# DDR3_16bits.net
KiCad netlist of a schematic drawn in Altium Designer
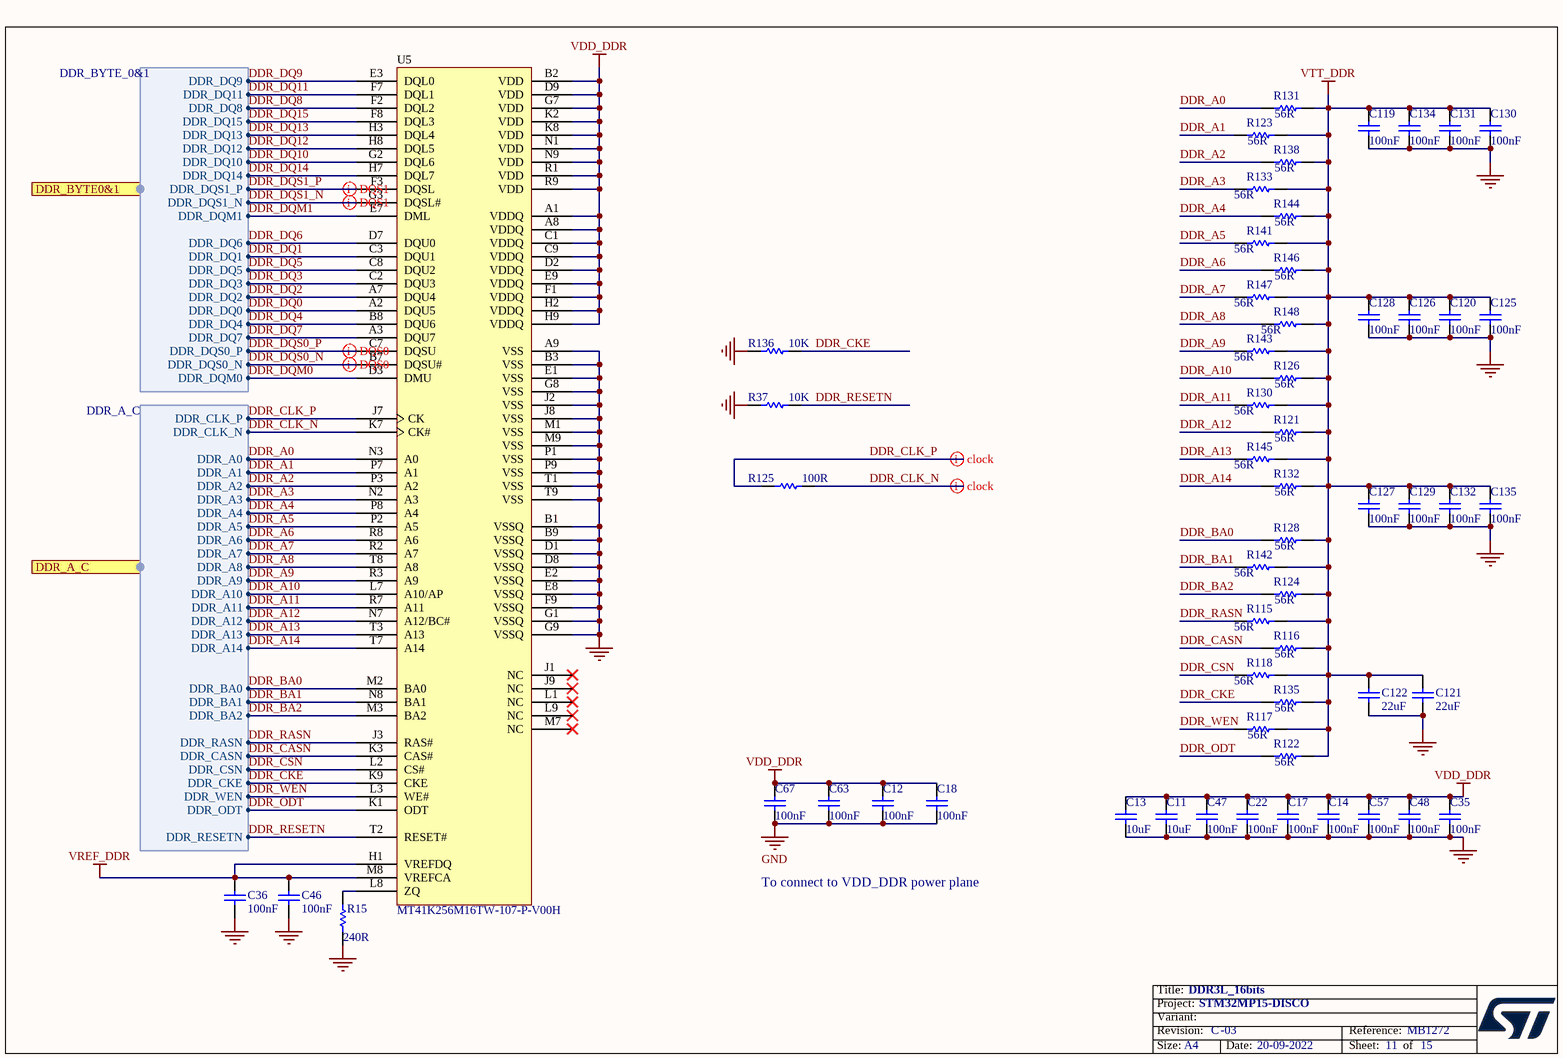
[diagram p0: DDR3_16bits.SchDoc]

(export (version "E")
  (design (tool "Eeschema 10.0.6"))
  (components
    (comp (ref "C11")
      (value "10uF")
      (footprint "C0603")
      (description "Capacitor, MLCC, 10uF, 10V, X5R, 10%, 0603, T=0,8mm")
      (fields
        (field (name "INTERNAL_PART_NUMBER") "MCD-00099")
        (field (name "MANUFACTURER_PART_NUMBER") "GRM188R61A106KE69D")
        (field (name "PROVIDED_BY") "SUBCO")
      )
      (libsource (lib "MCD_PARTS_database") (part "Capacitor"))
    )
    (comp (ref "C12")
      (value "100nF")
      (footprint "C0402")
      (description "Capacitor, MLCC, 100nF, 16V, X7R, 10%, 0402, T=0.5mm")
      (fields
        (field (name "INTERNAL_PART_NUMBER") "MCD-00006")
        (field (name "MANUFACTURER_PART_NUMBER") "CC0402KRX7R7BB104")
        (field (name "PROVIDED_BY") "SUBCO")
      )
      (libsource (lib "MCD_PARTS_database") (part "Capacitor"))
    )
    (comp (ref "C13")
      (value "10uF")
      (footprint "C0603")
      (description "Capacitor, MLCC, 10uF, 10V, X5R, 10%, 0603, T=0,8mm")
      (fields
        (field (name "INTERNAL_PART_NUMBER") "MCD-00099")
        (field (name "MANUFACTURER_PART_NUMBER") "GRM188R61A106KE69D")
        (field (name "PROVIDED_BY") "SUBCO")
      )
      (libsource (lib "MCD_PARTS_database") (part "Capacitor"))
    )
    (comp (ref "C14")
      (value "100nF")
      (footprint "C0402")
      (description "Capacitor,100nF,16V,X7R,10%,0402")
      (fields
        (field (name "INTERNAL_PART_NUMBER") "MCD-00006")
        (field (name "MANUFACTURER_PART_NUMBER") "CC0402KRX7R7BB104")
        (field (name "PROVIDED_BY") "SUBCO")
      )
      (libsource (lib "MCD_PARTS_database") (part "Capacitor"))
    )
    (comp (ref "C17")
      (value "100nF")
      (footprint "C0402")
      (description "Capacitor,100nF,16V,X7R,10%,0402")
      (fields
        (field (name "INTERNAL_PART_NUMBER") "MCD-00006")
        (field (name "MANUFACTURER_PART_NUMBER") "CC0402KRX7R7BB104")
        (field (name "PROVIDED_BY") "SUBCO")
      )
      (libsource (lib "MCD_PARTS_database") (part "Capacitor"))
    )
    (comp (ref "C18")
      (value "100nF")
      (footprint "C0402")
      (description "Capacitor, MLCC, 100nF, 16V, X7R, 10%, 0402, T=0.5mm")
      (fields
        (field (name "INTERNAL_PART_NUMBER") "MCD-00006")
        (field (name "MANUFACTURER_PART_NUMBER") "CC0402KRX7R7BB104")
        (field (name "PROVIDED_BY") "SUBCO")
      )
      (libsource (lib "MCD_PARTS_database") (part "Capacitor"))
    )
    (comp (ref "C22")
      (value "100nF")
      (footprint "C0402")
      (description "Capacitor,100nF,16V,X7R,10%,0402")
      (fields
        (field (name "INTERNAL_PART_NUMBER") "MCD-00006")
        (field (name "MANUFACTURER_PART_NUMBER") "CC0402KRX7R7BB104")
        (field (name "PROVIDED_BY") "SUBCO")
      )
      (libsource (lib "MCD_PARTS_database") (part "Capacitor"))
    )
    (comp (ref "C35")
      (value "100nF")
      (footprint "C0402")
      (description "Capacitor,100nF,16V,X7R,10%,0402")
      (fields
        (field (name "INTERNAL_PART_NUMBER") "MCD-00006")
        (field (name "MANUFACTURER_PART_NUMBER") "CC0402KRX7R7BB104")
        (field (name "PROVIDED_BY") "SUBCO")
      )
      (libsource (lib "MCD_PARTS_database") (part "Capacitor"))
    )
    (comp (ref "C36")
      (value "100nF")
      (footprint "C0402")
      (description "Capacitor,100nF,16V,X7R,10%,0402")
      (fields
        (field (name "INTERNAL_PART_NUMBER") "MCD-00006")
        (field (name "MANUFACTURER_PART_NUMBER") "CC0402KRX7R7BB104")
        (field (name "PROVIDED_BY") "SUBCO")
      )
      (libsource (lib "MCD_PARTS_database") (part "Capacitor"))
    )
    (comp (ref "C46")
      (value "100nF")
      (footprint "C0402")
      (description "Capacitor,100nF,16V,X7R,10%,0402")
      (fields
        (field (name "INTERNAL_PART_NUMBER") "MCD-00006")
        (field (name "MANUFACTURER_PART_NUMBER") "CC0402KRX7R7BB104")
        (field (name "PROVIDED_BY") "SUBCO")
      )
      (libsource (lib "MCD_PARTS_database") (part "Capacitor"))
    )
    (comp (ref "C47")
      (value "100nF")
      (footprint "C0402")
      (description "Capacitor,100nF,16V,X7R,10%,0402")
      (fields
        (field (name "INTERNAL_PART_NUMBER") "MCD-00006")
        (field (name "MANUFACTURER_PART_NUMBER") "CC0402KRX7R7BB104")
        (field (name "PROVIDED_BY") "SUBCO")
      )
      (libsource (lib "MCD_PARTS_database") (part "Capacitor"))
    )
    (comp (ref "C48")
      (value "100nF")
      (footprint "C0402")
      (description "Capacitor,100nF,16V,X7R,10%,0402")
      (fields
        (field (name "INTERNAL_PART_NUMBER") "MCD-00006")
        (field (name "MANUFACTURER_PART_NUMBER") "CC0402KRX7R7BB104")
        (field (name "PROVIDED_BY") "SUBCO")
      )
      (libsource (lib "MCD_PARTS_database") (part "Capacitor"))
    )
    (comp (ref "C57")
      (value "100nF")
      (footprint "C0402")
      (description "Capacitor,100nF,16V,X7R,10%,0402")
      (fields
        (field (name "INTERNAL_PART_NUMBER") "MCD-00006")
        (field (name "MANUFACTURER_PART_NUMBER") "CC0402KRX7R7BB104")
        (field (name "PROVIDED_BY") "SUBCO")
      )
      (libsource (lib "MCD_PARTS_database") (part "Capacitor"))
    )
    (comp (ref "C63")
      (value "100nF")
      (footprint "C0402")
      (description "Capacitor, MLCC, 100nF, 16V, X7R, 10%, 0402, T=0.5mm")
      (fields
        (field (name "INTERNAL_PART_NUMBER") "MCD-00006")
        (field (name "MANUFACTURER_PART_NUMBER") "CC0402KRX7R7BB104")
        (field (name "PROVIDED_BY") "SUBCO")
      )
      (libsource (lib "MCD_PARTS_database") (part "Capacitor"))
    )
    (comp (ref "C67")
      (value "100nF")
      (footprint "C0402")
      (description "Capacitor, MLCC, 100nF, 16V, X7R, 10%, 0402, T=0.5mm")
      (fields
        (field (name "INTERNAL_PART_NUMBER") "MCD-00006")
        (field (name "MANUFACTURER_PART_NUMBER") "CC0402KRX7R7BB104")
        (field (name "PROVIDED_BY") "SUBCO")
      )
      (libsource (lib "MCD_PARTS_database") (part "Capacitor"))
    )
    (comp (ref "C119")
      (value "100nF")
      (footprint "C0402")
      (description "Capacitor,100nF,16V,X7R,10%,0402")
      (fields
        (field (name "INTERNAL_PART_NUMBER") "MCD-00006")
        (field (name "MANUFACTURER_PART_NUMBER") "CC0402KRX7R7BB104")
        (field (name "PROVIDED_BY") "SUBCO")
      )
      (libsource (lib "MCD_PARTS_database") (part "Capacitor"))
    )
    (comp (ref "C120")
      (value "100nF")
      (footprint "C0402")
      (description "Capacitor,100nF,16V,X7R,10%,0402")
      (fields
        (field (name "INTERNAL_PART_NUMBER") "MCD-00006")
        (field (name "MANUFACTURER_PART_NUMBER") "CC0402KRX7R7BB104")
        (field (name "PROVIDED_BY") "SUBCO")
      )
      (libsource (lib "MCD_PARTS_database") (part "Capacitor"))
    )
    (comp (ref "C121")
      (value "22uF")
      (footprint "C0603")
      (description "Capacitor, MLCC, 22uF, 6V3, X5R, 20%, 0603, T=0,8mm")
      (fields
        (field (name "INTERNAL_PART_NUMBER") "MCD-00100")
        (field (name "MANUFACTURER_PART_NUMBER") "GRM188R60J226MEA0J")
        (field (name "PROVIDED_BY") "SUBCO")
      )
      (libsource (lib "MCD_PARTS_database") (part "Capacitor"))
    )
    (comp (ref "C122")
      (value "22uF")
      (footprint "C0603")
      (description "Capacitor, MLCC, 22uF, 6V3, X5R, 20%, 0603, T=0,8mm")
      (fields
        (field (name "INTERNAL_PART_NUMBER") "MCD-00100")
        (field (name "MANUFACTURER_PART_NUMBER") "GRM188R60J226MEA0J")
        (field (name "PROVIDED_BY") "SUBCO")
      )
      (libsource (lib "MCD_PARTS_database") (part "Capacitor"))
    )
    (comp (ref "C125")
      (value "100nF")
      (footprint "C0402")
      (description "Capacitor,100nF,16V,X7R,10%,0402")
      (fields
        (field (name "INTERNAL_PART_NUMBER") "MCD-00006")
        (field (name "MANUFACTURER_PART_NUMBER") "CC0402KRX7R7BB104")
        (field (name "PROVIDED_BY") "SUBCO")
      )
      (libsource (lib "MCD_PARTS_database") (part "Capacitor"))
    )
    (comp (ref "C126")
      (value "100nF")
      (footprint "C0402")
      (description "Capacitor,100nF,16V,X7R,10%,0402")
      (fields
        (field (name "INTERNAL_PART_NUMBER") "MCD-00006")
        (field (name "MANUFACTURER_PART_NUMBER") "CC0402KRX7R7BB104")
        (field (name "PROVIDED_BY") "SUBCO")
      )
      (libsource (lib "MCD_PARTS_database") (part "Capacitor"))
    )
    (comp (ref "C127")
      (value "100nF")
      (footprint "C0402")
      (description "Capacitor,100nF,16V,X7R,10%,0402")
      (fields
        (field (name "INTERNAL_PART_NUMBER") "MCD-00006")
        (field (name "MANUFACTURER_PART_NUMBER") "CC0402KRX7R7BB104")
        (field (name "PROVIDED_BY") "SUBCO")
      )
      (libsource (lib "MCD_PARTS_database") (part "Capacitor"))
    )
    (comp (ref "C128")
      (value "100nF")
      (footprint "C0402")
      (description "Capacitor,100nF,16V,X7R,10%,0402")
      (fields
        (field (name "INTERNAL_PART_NUMBER") "MCD-00006")
        (field (name "MANUFACTURER_PART_NUMBER") "CC0402KRX7R7BB104")
        (field (name "PROVIDED_BY") "SUBCO")
      )
      (libsource (lib "MCD_PARTS_database") (part "Capacitor"))
    )
    (comp (ref "C129")
      (value "100nF")
      (footprint "C0402")
      (description "Capacitor,100nF,16V,X7R,10%,0402")
      (fields
        (field (name "INTERNAL_PART_NUMBER") "MCD-00006")
        (field (name "MANUFACTURER_PART_NUMBER") "CC0402KRX7R7BB104")
        (field (name "PROVIDED_BY") "SUBCO")
      )
      (libsource (lib "MCD_PARTS_database") (part "Capacitor"))
    )
    (comp (ref "C130")
      (value "100nF")
      (footprint "C0402")
      (description "Capacitor,100nF,16V,X7R,10%,0402")
      (fields
        (field (name "INTERNAL_PART_NUMBER") "MCD-00006")
        (field (name "MANUFACTURER_PART_NUMBER") "CC0402KRX7R7BB104")
        (field (name "PROVIDED_BY") "SUBCO")
      )
      (libsource (lib "MCD_PARTS_database") (part "Capacitor"))
    )
    (comp (ref "C131")
      (value "100nF")
      (footprint "C0402")
      (description "Capacitor,100nF,16V,X7R,10%,0402")
      (fields
        (field (name "INTERNAL_PART_NUMBER") "MCD-00006")
        (field (name "MANUFACTURER_PART_NUMBER") "CC0402KRX7R7BB104")
        (field (name "PROVIDED_BY") "SUBCO")
      )
      (libsource (lib "MCD_PARTS_database") (part "Capacitor"))
    )
    (comp (ref "C132")
      (value "100nF")
      (footprint "C0402")
      (description "Capacitor,100nF,16V,X7R,10%,0402")
      (fields
        (field (name "INTERNAL_PART_NUMBER") "MCD-00006")
        (field (name "MANUFACTURER_PART_NUMBER") "CC0402KRX7R7BB104")
        (field (name "PROVIDED_BY") "SUBCO")
      )
      (libsource (lib "MCD_PARTS_database") (part "Capacitor"))
    )
    (comp (ref "C134")
      (value "100nF")
      (footprint "C0402")
      (description "Capacitor,100nF,16V,X7R,10%,0402")
      (fields
        (field (name "INTERNAL_PART_NUMBER") "MCD-00006")
        (field (name "MANUFACTURER_PART_NUMBER") "CC0402KRX7R7BB104")
        (field (name "PROVIDED_BY") "SUBCO")
      )
      (libsource (lib "MCD_PARTS_database") (part "Capacitor"))
    )
    (comp (ref "C135")
      (value "100nF")
      (footprint "C0402")
      (description "Capacitor,100nF,16V,X7R,10%,0402")
      (fields
        (field (name "INTERNAL_PART_NUMBER") "MCD-00006")
        (field (name "MANUFACTURER_PART_NUMBER") "CC0402KRX7R7BB104")
        (field (name "PROVIDED_BY") "SUBCO")
      )
      (libsource (lib "MCD_PARTS_database") (part "Capacitor"))
    )
    (comp (ref "R15")
      (value "240R")
      (footprint "R0402")
      (description "Resistor,240R,0402,1%,1/16W")
      (fields
        (field (name "INTERNAL_PART_NUMBER") "MCD-00120")
        (field (name "MANUFACTURER_PART_NUMBER") "RC0402FR-07240RL")
        (field (name "PROVIDED_BY") "SUBCO")
      )
      (libsource (lib "MCD_PARTS_database") (part "Resistor"))
    )
    (comp (ref "R37")
      (value "10K")
      (footprint "R0402")
      (description "Resistor,10K,0402,1%,1/16W")
      (fields
        (field (name "INTERNAL_PART_NUMBER") "MCD-00053")
        (field (name "MANUFACTURER_PART_NUMBER") "RC0402FR-0710KL")
        (field (name "PROVIDED_BY") "SUBCO")
      )
      (libsource (lib "MCD_PARTS_database") (part "Resistor"))
    )
    (comp (ref "R115")
      (value "56R")
      (footprint "R0402")
      (description "Resistor, 56R, 0402, +/-1%, 1/16W")
      (fields
        (field (name "INTERNAL_PART_NUMBER") "MCD-00054")
        (field (name "MANUFACTURER_PART_NUMBER") "RC0402FR-0756RL")
      )
      (libsource (lib "MCD_PARTS_database") (part "Resistor"))
    )
    (comp (ref "R116")
      (value "56R")
      (footprint "R0402")
      (description "Resistor, 56R, 0402, +/-1%, 1/16W")
      (fields
        (field (name "INTERNAL_PART_NUMBER") "MCD-00054")
        (field (name "MANUFACTURER_PART_NUMBER") "RC0402FR-0756RL")
      )
      (libsource (lib "MCD_PARTS_database") (part "Resistor"))
    )
    (comp (ref "R117")
      (value "56R")
      (footprint "R0402")
      (description "Resistor, 56R, 0402, +/-1%, 1/16W")
      (fields
        (field (name "INTERNAL_PART_NUMBER") "MCD-00054")
        (field (name "MANUFACTURER_PART_NUMBER") "RC0402FR-0756RL")
      )
      (libsource (lib "MCD_PARTS_database") (part "Resistor"))
    )
    (comp (ref "R118")
      (value "56R")
      (footprint "R0402")
      (description "Resistor, 56R, 0402, +/-1%, 1/16W")
      (fields
        (field (name "INTERNAL_PART_NUMBER") "MCD-00054")
        (field (name "MANUFACTURER_PART_NUMBER") "RC0402FR-0756RL")
      )
      (libsource (lib "MCD_PARTS_database") (part "Resistor"))
    )
    (comp (ref "R121")
      (value "56R")
      (footprint "R0402")
      (description "Resistor, 56R, 0402, +/-1%, 1/16W")
      (fields
        (field (name "INTERNAL_PART_NUMBER") "MCD-00054")
        (field (name "MANUFACTURER_PART_NUMBER") "RC0402FR-0756RL")
      )
      (libsource (lib "MCD_PARTS_database") (part "Resistor"))
    )
    (comp (ref "R122")
      (value "56R")
      (footprint "R0402")
      (description "Resistor, 56R, 0402, +/-1%, 1/16W")
      (fields
        (field (name "INTERNAL_PART_NUMBER") "MCD-00054")
        (field (name "MANUFACTURER_PART_NUMBER") "RC0402FR-0756RL")
      )
      (libsource (lib "MCD_PARTS_database") (part "Resistor"))
    )
    (comp (ref "R123")
      (value "56R")
      (footprint "R0402")
      (description "Resistor, 56R, 0402, +/-1%, 1/16W")
      (fields
        (field (name "INTERNAL_PART_NUMBER") "MCD-00054")
        (field (name "MANUFACTURER_PART_NUMBER") "RC0402FR-0756RL")
      )
      (libsource (lib "MCD_PARTS_database") (part "Resistor"))
    )
    (comp (ref "R124")
      (value "56R")
      (footprint "R0402")
      (description "Resistor, 56R, 0402, +/-1%, 1/16W")
      (fields
        (field (name "INTERNAL_PART_NUMBER") "MCD-00054")
        (field (name "MANUFACTURER_PART_NUMBER") "RC0402FR-0756RL")
      )
      (libsource (lib "MCD_PARTS_database") (part "Resistor"))
    )
    (comp (ref "R125")
      (value "100R")
      (footprint "R0402")
      (description "Resistor,100R,0402,1%,1/16W")
      (fields
        (field (name "INTERNAL_PART_NUMBER") "MCD-00067")
        (field (name "MANUFACTURER_PART_NUMBER") "RC0402FR-07100RL")
        (field (name "PROVIDED_BY") "SUBCO")
      )
      (libsource (lib "MCD_PARTS_database") (part "Resistor"))
    )
    (comp (ref "R126")
      (value "56R")
      (footprint "R0402")
      (description "Resistor, 56R, 0402, +/-1%, 1/16W")
      (fields
        (field (name "INTERNAL_PART_NUMBER") "MCD-00054")
        (field (name "MANUFACTURER_PART_NUMBER") "RC0402FR-0756RL")
      )
      (libsource (lib "MCD_PARTS_database") (part "Resistor"))
    )
    (comp (ref "R128")
      (value "56R")
      (footprint "R0402")
      (description "Resistor, 56R, 0402, +/-1%, 1/16W")
      (fields
        (field (name "INTERNAL_PART_NUMBER") "MCD-00054")
        (field (name "MANUFACTURER_PART_NUMBER") "RC0402FR-0756RL")
      )
      (libsource (lib "MCD_PARTS_database") (part "Resistor"))
    )
    (comp (ref "R130")
      (value "56R")
      (footprint "R0402")
      (description "Resistor, 56R, 0402, +/-1%, 1/16W")
      (fields
        (field (name "INTERNAL_PART_NUMBER") "MCD-00054")
        (field (name "MANUFACTURER_PART_NUMBER") "RC0402FR-0756RL")
      )
      (libsource (lib "MCD_PARTS_database") (part "Resistor"))
    )
    (comp (ref "R131")
      (value "56R")
      (footprint "R0402")
      (description "Resistor, 56R, 0402, +/-1%, 1/16W")
      (fields
        (field (name "INTERNAL_PART_NUMBER") "MCD-00054")
        (field (name "MANUFACTURER_PART_NUMBER") "RC0402FR-0756RL")
      )
      (libsource (lib "MCD_PARTS_database") (part "Resistor"))
    )
    (comp (ref "R132")
      (value "56R")
      (footprint "R0402")
      (description "Resistor, 56R, 0402, +/-1%, 1/16W")
      (fields
        (field (name "INTERNAL_PART_NUMBER") "MCD-00054")
        (field (name "MANUFACTURER_PART_NUMBER") "RC0402FR-0756RL")
      )
      (libsource (lib "MCD_PARTS_database") (part "Resistor"))
    )
    (comp (ref "R133")
      (value "56R")
      (footprint "R0402")
      (description "Resistor, 56R, 0402, +/-1%, 1/16W")
      (fields
        (field (name "INTERNAL_PART_NUMBER") "MCD-00054")
        (field (name "MANUFACTURER_PART_NUMBER") "RC0402FR-0756RL")
      )
      (libsource (lib "MCD_PARTS_database") (part "Resistor"))
    )
    (comp (ref "R135")
      (value "56R")
      (footprint "R0402")
      (description "Resistor, 56R, 0402, +/-1%, 1/16W")
      (fields
        (field (name "INTERNAL_PART_NUMBER") "MCD-00054")
        (field (name "MANUFACTURER_PART_NUMBER") "RC0402FR-0756RL")
      )
      (libsource (lib "MCD_PARTS_database") (part "Resistor"))
    )
    (comp (ref "R136")
      (value "10K")
      (footprint "R0402")
      (description "Resistor,10K,0402,1%,1/16W")
      (fields
        (field (name "INTERNAL_PART_NUMBER") "MCD-00053")
        (field (name "MANUFACTURER_PART_NUMBER") "RC0402FR-0710KL")
        (field (name "PROVIDED_BY") "SUBCO")
      )
      (libsource (lib "MCD_PARTS_database") (part "Resistor"))
    )
    (comp (ref "R138")
      (value "56R")
      (footprint "R0402")
      (description "Resistor, 56R, 0402, +/-1%, 1/16W")
      (fields
        (field (name "INTERNAL_PART_NUMBER") "MCD-00054")
        (field (name "MANUFACTURER_PART_NUMBER") "RC0402FR-0756RL")
      )
      (libsource (lib "MCD_PARTS_database") (part "Resistor"))
    )
    (comp (ref "R141")
      (value "56R")
      (footprint "R0402")
      (description "Resistor, 56R, 0402, +/-1%, 1/16W")
      (fields
        (field (name "INTERNAL_PART_NUMBER") "MCD-00054")
        (field (name "MANUFACTURER_PART_NUMBER") "RC0402FR-0756RL")
      )
      (libsource (lib "MCD_PARTS_database") (part "Resistor"))
    )
    (comp (ref "R142")
      (value "56R")
      (footprint "R0402")
      (description "Resistor, 56R, 0402, +/-1%, 1/16W")
      (fields
        (field (name "INTERNAL_PART_NUMBER") "MCD-00054")
        (field (name "MANUFACTURER_PART_NUMBER") "RC0402FR-0756RL")
      )
      (libsource (lib "MCD_PARTS_database") (part "Resistor"))
    )
    (comp (ref "R143")
      (value "56R")
      (footprint "R0402")
      (description "Resistor, 56R, 0402, +/-1%, 1/16W")
      (fields
        (field (name "INTERNAL_PART_NUMBER") "MCD-00054")
        (field (name "MANUFACTURER_PART_NUMBER") "RC0402FR-0756RL")
      )
      (libsource (lib "MCD_PARTS_database") (part "Resistor"))
    )
    (comp (ref "R144")
      (value "56R")
      (footprint "R0402")
      (description "Resistor, 56R, 0402, +/-1%, 1/16W")
      (fields
        (field (name "INTERNAL_PART_NUMBER") "MCD-00054")
        (field (name "MANUFACTURER_PART_NUMBER") "RC0402FR-0756RL")
      )
      (libsource (lib "MCD_PARTS_database") (part "Resistor"))
    )
    (comp (ref "R145")
      (value "56R")
      (footprint "R0402")
      (description "Resistor, 56R, 0402, +/-1%, 1/16W")
      (fields
        (field (name "INTERNAL_PART_NUMBER") "MCD-00054")
        (field (name "MANUFACTURER_PART_NUMBER") "RC0402FR-0756RL")
      )
      (libsource (lib "MCD_PARTS_database") (part "Resistor"))
    )
    (comp (ref "R146")
      (value "56R")
      (footprint "R0402")
      (description "Resistor, 56R, 0402, +/-1%, 1/16W")
      (fields
        (field (name "INTERNAL_PART_NUMBER") "MCD-00054")
        (field (name "MANUFACTURER_PART_NUMBER") "RC0402FR-0756RL")
      )
      (libsource (lib "MCD_PARTS_database") (part "Resistor"))
    )
    (comp (ref "R147")
      (value "56R")
      (footprint "R0402")
      (description "Resistor, 56R, 0402, +/-1%, 1/16W")
      (fields
        (field (name "INTERNAL_PART_NUMBER") "MCD-00054")
        (field (name "MANUFACTURER_PART_NUMBER") "RC0402FR-0756RL")
      )
      (libsource (lib "MCD_PARTS_database") (part "Resistor"))
    )
    (comp (ref "R148")
      (value "56R")
      (footprint "R0402")
      (description "Resistor, 56R, 0402, +/-1%, 1/16W")
      (fields
        (field (name "INTERNAL_PART_NUMBER") "MCD-00054")
        (field (name "MANUFACTURER_PART_NUMBER") "RC0402FR-0756RL")
      )
      (libsource (lib "MCD_PARTS_database") (part "Resistor"))
    )
    (comp (ref "U5")
      (value "MT41K256M16TW-107-P-V00H")
      (footprint "ICC_FBGA96_8X14_P080")
      (description "Memory,DDR3L,4Gb,256Mbx16,1866MT/s,1V35,FBGA96")
      (fields
        (field (name "INTERNAL_PART_NUMBER") "MCD-00207")
        (field (name "MANUFACTURER") "MICRON")
        (field (name "PROVIDED_BY") "SUBCO")
      )
      (libsource (lib "MCD_PARTS_database") (part "MT41K256M16TW-107{colon}P - V00H"))
    )
  )
  (nets
    (net (code "3") (name "/DDR_A0") (class "Default")
      (node (ref "R131") (pin "1") (pinfunction "1_1") (pintype "passive"))
      (node (ref "U5") (pin "N3") (pinfunction "A0_N3") (pintype "passive"))
    )
    (net (code "4") (name "/DDR_A1") (class "Default")
      (node (ref "R123") (pin "1") (pinfunction "1_1") (pintype "passive"))
      (node (ref "U5") (pin "P7") (pinfunction "A1_P7") (pintype "passive"))
    )
    (net (code "5") (name "/DDR_A2") (class "Default")
      (node (ref "R138") (pin "1") (pinfunction "1_1") (pintype "passive"))
      (node (ref "U5") (pin "P3") (pinfunction "A2_P3") (pintype "passive"))
    )
    (net (code "6") (name "/DDR_A3") (class "Default")
      (node (ref "R133") (pin "1") (pinfunction "1_1") (pintype "passive"))
      (node (ref "U5") (pin "N2") (pinfunction "A3_N2") (pintype "passive"))
    )
    (net (code "7") (name "/DDR_A4") (class "Default")
      (node (ref "R144") (pin "1") (pinfunction "1_1") (pintype "passive"))
      (node (ref "U5") (pin "P8") (pinfunction "A4_P8") (pintype "passive"))
    )
    (net (code "8") (name "/DDR_A5") (class "Default")
      (node (ref "R141") (pin "1") (pinfunction "1_1") (pintype "passive"))
      (node (ref "U5") (pin "P2") (pinfunction "A5_P2") (pintype "passive"))
    )
    (net (code "9") (name "/DDR_A6") (class "Default")
      (node (ref "R146") (pin "1") (pinfunction "1_1") (pintype "passive"))
      (node (ref "U5") (pin "R8") (pinfunction "A6_R8") (pintype "passive"))
    )
    (net (code "10") (name "/DDR_A7") (class "Default")
      (node (ref "R147") (pin "1") (pinfunction "1_1") (pintype "passive"))
      (node (ref "U5") (pin "R2") (pinfunction "A7_R2") (pintype "passive"))
    )
    (net (code "11") (name "/DDR_A8") (class "Default")
      (node (ref "R148") (pin "1") (pinfunction "1_1") (pintype "passive"))
      (node (ref "U5") (pin "T8") (pinfunction "A8_T8") (pintype "passive"))
    )
    (net (code "12") (name "/DDR_A9") (class "Default")
      (node (ref "R143") (pin "1") (pinfunction "1_1") (pintype "passive"))
      (node (ref "U5") (pin "R3") (pinfunction "A9_R3") (pintype "passive"))
    )
    (net (code "13") (name "/DDR_A10") (class "Default")
      (node (ref "R126") (pin "1") (pinfunction "1_1") (pintype "passive"))
      (node (ref "U5") (pin "L7") (pinfunction "A10/AP_L7") (pintype "passive"))
    )
    (net (code "14") (name "/DDR_A11") (class "Default")
      (node (ref "R130") (pin "1") (pinfunction "1_1") (pintype "passive"))
      (node (ref "U5") (pin "R7") (pinfunction "A11_R7") (pintype "passive"))
    )
    (net (code "15") (name "/DDR_A12") (class "Default")
      (node (ref "R121") (pin "1") (pinfunction "1_1") (pintype "passive"))
      (node (ref "U5") (pin "N7") (pinfunction "A12/BC#_N7") (pintype "passive"))
    )
    (net (code "16") (name "/DDR_A13") (class "Default")
      (node (ref "R145") (pin "1") (pinfunction "1_1") (pintype "passive"))
      (node (ref "U5") (pin "T3") (pinfunction "A13_T3") (pintype "passive"))
    )
    (net (code "17") (name "/DDR_A14") (class "Default")
      (node (ref "R132") (pin "1") (pinfunction "1_1") (pintype "passive"))
      (node (ref "U5") (pin "T7") (pinfunction "A14_T7") (pintype "passive"))
    )
    (net (code "18") (name "/DDR_BA0") (class "Default")
      (node (ref "R128") (pin "1") (pinfunction "1_1") (pintype "passive"))
      (node (ref "U5") (pin "M2") (pinfunction "BA0_M2") (pintype "passive"))
    )
    (net (code "19") (name "/DDR_BA1") (class "Default")
      (node (ref "R142") (pin "1") (pinfunction "1_1") (pintype "passive"))
      (node (ref "U5") (pin "N8") (pinfunction "BA1_N8") (pintype "passive"))
    )
    (net (code "20") (name "/DDR_BA2") (class "Default")
      (node (ref "R124") (pin "1") (pinfunction "1_1") (pintype "passive"))
      (node (ref "U5") (pin "M3") (pinfunction "BA2_M3") (pintype "passive"))
    )
    (net (code "21") (name "/DDR_CASN") (class "Default")
      (node (ref "R116") (pin "1") (pinfunction "1_1") (pintype "passive"))
      (node (ref "U5") (pin "K3") (pinfunction "CAS#_K3") (pintype "passive"))
    )
    (net (code "22") (name "/DDR_CKE") (class "Default")
      (node (ref "R135") (pin "1") (pinfunction "1_1") (pintype "passive"))
      (node (ref "R136") (pin "2") (pinfunction "2_2") (pintype "passive"))
      (node (ref "U5") (pin "K9") (pinfunction "CKE_K9") (pintype "passive"))
    )
    (net (code "23") (name "/DDR_CLK_N") (class "Default")
      (node (ref "R125") (pin "2") (pinfunction "2_2") (pintype "passive"))
      (node (ref "U5") (pin "K7") (pinfunction "CK#_K7") (pintype "passive"))
    )
    (net (code "24") (name "/DDR_CLK_P") (class "Default")
      (node (ref "R125") (pin "1") (pinfunction "1_1") (pintype "passive"))
      (node (ref "U5") (pin "J7") (pinfunction "CK_J7") (pintype "passive"))
    )
    (net (code "25") (name "/DDR_CSN") (class "Default")
      (node (ref "R118") (pin "1") (pinfunction "1_1") (pintype "passive"))
      (node (ref "U5") (pin "L2") (pinfunction "CS#_L2") (pintype "passive"))
    )
    (net (code "26") (name "/DDR_DQ0") (class "Default")
      (node (ref "U5") (pin "A2") (pinfunction "DQU5_A2") (pintype "passive"))
    )
    (net (code "27") (name "/DDR_DQ1") (class "Default")
      (node (ref "U5") (pin "C3") (pinfunction "DQU1_C3") (pintype "passive"))
    )
    (net (code "28") (name "/DDR_DQ2") (class "Default")
      (node (ref "U5") (pin "A7") (pinfunction "DQU4_A7") (pintype "passive"))
    )
    (net (code "29") (name "/DDR_DQ3") (class "Default")
      (node (ref "U5") (pin "C2") (pinfunction "DQU3_C2") (pintype "passive"))
    )
    (net (code "30") (name "/DDR_DQ4") (class "Default")
      (node (ref "U5") (pin "B8") (pinfunction "DQU6_B8") (pintype "passive"))
    )
    (net (code "31") (name "/DDR_DQ5") (class "Default")
      (node (ref "U5") (pin "C8") (pinfunction "DQU2_C8") (pintype "passive"))
    )
    (net (code "32") (name "/DDR_DQ6") (class "Default")
      (node (ref "U5") (pin "D7") (pinfunction "DQU0_D7") (pintype "passive"))
    )
    (net (code "33") (name "/DDR_DQ7") (class "Default")
      (node (ref "U5") (pin "A3") (pinfunction "DQU7_A3") (pintype "passive"))
    )
    (net (code "34") (name "/DDR_DQ8") (class "Default")
      (node (ref "U5") (pin "F2") (pinfunction "DQL2_F2") (pintype "passive"))
    )
    (net (code "35") (name "/DDR_DQ9") (class "Default")
      (node (ref "U5") (pin "E3") (pinfunction "DQL0_E3") (pintype "passive"))
    )
    (net (code "36") (name "/DDR_DQ10") (class "Default")
      (node (ref "U5") (pin "G2") (pinfunction "DQL6_G2") (pintype "passive"))
    )
    (net (code "37") (name "/DDR_DQ11") (class "Default")
      (node (ref "U5") (pin "F7") (pinfunction "DQL1_F7") (pintype "passive"))
    )
    (net (code "38") (name "/DDR_DQ12") (class "Default")
      (node (ref "U5") (pin "H8") (pinfunction "DQL5_H8") (pintype "passive"))
    )
    (net (code "39") (name "/DDR_DQ13") (class "Default")
      (node (ref "U5") (pin "H3") (pinfunction "DQL4_H3") (pintype "passive"))
    )
    (net (code "40") (name "/DDR_DQ14") (class "Default")
      (node (ref "U5") (pin "H7") (pinfunction "DQL7_H7") (pintype "passive"))
    )
    (net (code "41") (name "/DDR_DQ15") (class "Default")
      (node (ref "U5") (pin "F8") (pinfunction "DQL3_F8") (pintype "passive"))
    )
    (net (code "42") (name "/DDR_DQM0") (class "Default")
      (node (ref "U5") (pin "D3") (pinfunction "DMU_D3") (pintype "passive"))
    )
    (net (code "43") (name "/DDR_DQM1") (class "Default")
      (node (ref "U5") (pin "E7") (pinfunction "DML_E7") (pintype "passive"))
    )
    (net (code "44") (name "/DDR_DQS0_N") (class "Default")
      (node (ref "U5") (pin "B7") (pinfunction "DQSU#_B7") (pintype "passive"))
    )
    (net (code "45") (name "/DDR_DQS0_P") (class "Default")
      (node (ref "U5") (pin "C7") (pinfunction "DQSU_C7") (pintype "passive"))
    )
    (net (code "46") (name "/DDR_DQS1_N") (class "Default")
      (node (ref "U5") (pin "G3") (pinfunction "DQSL#_G3") (pintype "passive"))
    )
    (net (code "47") (name "/DDR_DQS1_P") (class "Default")
      (node (ref "U5") (pin "F3") (pinfunction "DQSL_F3") (pintype "passive"))
    )
    (net (code "48") (name "/DDR_ODT") (class "Default")
      (node (ref "R122") (pin "1") (pinfunction "1_1") (pintype "passive"))
      (node (ref "U5") (pin "K1") (pinfunction "ODT_K1") (pintype "passive"))
    )
    (net (code "49") (name "/DDR_RASN") (class "Default")
      (node (ref "R115") (pin "1") (pinfunction "1_1") (pintype "passive"))
      (node (ref "U5") (pin "J3") (pinfunction "RAS#_J3") (pintype "passive"))
    )
    (net (code "50") (name "/DDR_RESETN") (class "Default")
      (node (ref "R37") (pin "2") (pinfunction "2_2") (pintype "passive"))
      (node (ref "U5") (pin "T2") (pinfunction "RESET#_T2") (pintype "passive"))
    )
    (net (code "51") (name "/DDR_WEN") (class "Default")
      (node (ref "R117") (pin "1") (pinfunction "1_1") (pintype "passive"))
      (node (ref "U5") (pin "L3") (pinfunction "WE#_L3") (pintype "passive"))
    )
    (net (code "54") (name "GND") (class "Default")
      (node (ref "C11") (pin "1") (pinfunction "1_1") (pintype "passive"))
      (node (ref "C119") (pin "2") (pinfunction "2_2") (pintype "passive"))
      (node (ref "C12") (pin "1") (pinfunction "1_1") (pintype "passive"))
      (node (ref "C120") (pin "2") (pinfunction "2_2") (pintype "passive"))
      (node (ref "C121") (pin "1") (pinfunction "1_1") (pintype "passive"))
      (node (ref "C122") (pin "1") (pinfunction "1_1") (pintype "passive"))
      (node (ref "C125") (pin "2") (pinfunction "2_2") (pintype "passive"))
      (node (ref "C126") (pin "2") (pinfunction "2_2") (pintype "passive"))
      (node (ref "C127") (pin "2") (pinfunction "2_2") (pintype "passive"))
      (node (ref "C128") (pin "2") (pinfunction "2_2") (pintype "passive"))
      (node (ref "C129") (pin "2") (pinfunction "2_2") (pintype "passive"))
      (node (ref "C13") (pin "1") (pinfunction "1_1") (pintype "passive"))
      (node (ref "C130") (pin "2") (pinfunction "2_2") (pintype "passive"))
      (node (ref "C131") (pin "2") (pinfunction "2_2") (pintype "passive"))
      (node (ref "C132") (pin "2") (pinfunction "2_2") (pintype "passive"))
      (node (ref "C134") (pin "2") (pinfunction "2_2") (pintype "passive"))
      (node (ref "C135") (pin "2") (pinfunction "2_2") (pintype "passive"))
      (node (ref "C14") (pin "2") (pinfunction "2_2") (pintype "passive"))
      (node (ref "C17") (pin "2") (pinfunction "2_2") (pintype "passive"))
      (node (ref "C18") (pin "1") (pinfunction "1_1") (pintype "passive"))
      (node (ref "C22") (pin "2") (pinfunction "2_2") (pintype "passive"))
      (node (ref "C35") (pin "2") (pinfunction "2_2") (pintype "passive"))
      (node (ref "C36") (pin "2") (pinfunction "2_2") (pintype "passive"))
      (node (ref "C46") (pin "2") (pinfunction "2_2") (pintype "passive"))
      (node (ref "C47") (pin "2") (pinfunction "2_2") (pintype "passive"))
      (node (ref "C48") (pin "2") (pinfunction "2_2") (pintype "passive"))
      (node (ref "C57") (pin "2") (pinfunction "2_2") (pintype "passive"))
      (node (ref "C63") (pin "1") (pinfunction "1_1") (pintype "passive"))
      (node (ref "C67") (pin "1") (pinfunction "1_1") (pintype "passive"))
      (node (ref "R136") (pin "1") (pinfunction "1_1") (pintype "passive"))
      (node (ref "R15") (pin "1") (pinfunction "1_1") (pintype "passive"))
      (node (ref "R37") (pin "1") (pinfunction "1_1") (pintype "passive"))
      (node (ref "U5") (pin "A9") (pinfunction "VSS_A9") (pintype "passive"))
      (node (ref "U5") (pin "B1") (pinfunction "VSSQ_B1") (pintype "passive"))
      (node (ref "U5") (pin "B3") (pinfunction "VSS_B3") (pintype "passive"))
      (node (ref "U5") (pin "B9") (pinfunction "VSSQ_B9") (pintype "passive"))
      (node (ref "U5") (pin "D1") (pinfunction "VSSQ_D1") (pintype "passive"))
      (node (ref "U5") (pin "D8") (pinfunction "VSSQ_D8") (pintype "passive"))
      (node (ref "U5") (pin "E1") (pinfunction "VSS_E1") (pintype "passive"))
      (node (ref "U5") (pin "E2") (pinfunction "VSSQ_E2") (pintype "passive"))
      (node (ref "U5") (pin "E8") (pinfunction "VSSQ_E8") (pintype "passive"))
      (node (ref "U5") (pin "F9") (pinfunction "VSSQ_F9") (pintype "passive"))
      (node (ref "U5") (pin "G1") (pinfunction "VSSQ_G1") (pintype "passive"))
      (node (ref "U5") (pin "G8") (pinfunction "VSS_G8") (pintype "passive"))
      (node (ref "U5") (pin "G9") (pinfunction "VSSQ_G9") (pintype "passive"))
      (node (ref "U5") (pin "J2") (pinfunction "VSS_J2") (pintype "passive"))
      (node (ref "U5") (pin "J8") (pinfunction "VSS_J8") (pintype "passive"))
      (node (ref "U5") (pin "M1") (pinfunction "VSS_M1") (pintype "passive"))
      (node (ref "U5") (pin "M9") (pinfunction "VSS_M9") (pintype "passive"))
      (node (ref "U5") (pin "P1") (pinfunction "VSS_P1") (pintype "passive"))
      (node (ref "U5") (pin "P9") (pinfunction "VSS_P9") (pintype "passive"))
      (node (ref "U5") (pin "T1") (pinfunction "VSS_T1") (pintype "passive"))
      (node (ref "U5") (pin "T9") (pinfunction "VSS_T9") (pintype "passive"))
    )
    (net (code "55") (name "Net-(U5-ZQ)") (class "Default")
      (node (ref "R15") (pin "2") (pinfunction "2_2") (pintype "passive"))
      (node (ref "U5") (pin "L8") (pinfunction "ZQ_L8") (pintype "passive"))
    )
    (net (code "56") (name "VDD_DDR") (class "Default")
      (node (ref "C11") (pin "2") (pinfunction "2_2") (pintype "passive"))
      (node (ref "C12") (pin "2") (pinfunction "2_2") (pintype "passive"))
      (node (ref "C13") (pin "2") (pinfunction "2_2") (pintype "passive"))
      (node (ref "C14") (pin "1") (pinfunction "1_1") (pintype "passive"))
      (node (ref "C17") (pin "1") (pinfunction "1_1") (pintype "passive"))
      (node (ref "C18") (pin "2") (pinfunction "2_2") (pintype "passive"))
      (node (ref "C22") (pin "1") (pinfunction "1_1") (pintype "passive"))
      (node (ref "C35") (pin "1") (pinfunction "1_1") (pintype "passive"))
      (node (ref "C47") (pin "1") (pinfunction "1_1") (pintype "passive"))
      (node (ref "C48") (pin "1") (pinfunction "1_1") (pintype "passive"))
      (node (ref "C57") (pin "1") (pinfunction "1_1") (pintype "passive"))
      (node (ref "C63") (pin "2") (pinfunction "2_2") (pintype "passive"))
      (node (ref "C67") (pin "2") (pinfunction "2_2") (pintype "passive"))
      (node (ref "U5") (pin "A1") (pinfunction "VDDQ_A1") (pintype "passive"))
      (node (ref "U5") (pin "A8") (pinfunction "VDDQ_A8") (pintype "passive"))
      (node (ref "U5") (pin "B2") (pinfunction "VDD_B2") (pintype "passive"))
      (node (ref "U5") (pin "C1") (pinfunction "VDDQ_C1") (pintype "passive"))
      (node (ref "U5") (pin "C9") (pinfunction "VDDQ_C9") (pintype "passive"))
      (node (ref "U5") (pin "D2") (pinfunction "VDDQ_D2") (pintype "passive"))
      (node (ref "U5") (pin "D9") (pinfunction "VDD_D9") (pintype "passive"))
      (node (ref "U5") (pin "E9") (pinfunction "VDDQ_E9") (pintype "passive"))
      (node (ref "U5") (pin "F1") (pinfunction "VDDQ_F1") (pintype "passive"))
      (node (ref "U5") (pin "G7") (pinfunction "VDD_G7") (pintype "passive"))
      (node (ref "U5") (pin "H2") (pinfunction "VDDQ_H2") (pintype "passive"))
      (node (ref "U5") (pin "H9") (pinfunction "VDDQ_H9") (pintype "passive"))
      (node (ref "U5") (pin "K2") (pinfunction "VDD_K2") (pintype "passive"))
      (node (ref "U5") (pin "K8") (pinfunction "VDD_K8") (pintype "passive"))
      (node (ref "U5") (pin "N1") (pinfunction "VDD_N1") (pintype "passive"))
      (node (ref "U5") (pin "N9") (pinfunction "VDD_N9") (pintype "passive"))
      (node (ref "U5") (pin "R1") (pinfunction "VDD_R1") (pintype "passive"))
      (node (ref "U5") (pin "R9") (pinfunction "VDD_R9") (pintype "passive"))
    )
    (net (code "57") (name "VREF_DDR") (class "Default")
      (node (ref "C36") (pin "1") (pinfunction "1_1") (pintype "passive"))
      (node (ref "C46") (pin "1") (pinfunction "1_1") (pintype "passive"))
      (node (ref "U5") (pin "H1") (pinfunction "VREFDQ_H1") (pintype "passive"))
      (node (ref "U5") (pin "M8") (pinfunction "VREFCA_M8") (pintype "passive"))
    )
    (net (code "58") (name "VTT_DDR") (class "Default")
      (node (ref "C119") (pin "1") (pinfunction "1_1") (pintype "passive"))
      (node (ref "C120") (pin "1") (pinfunction "1_1") (pintype "passive"))
      (node (ref "C121") (pin "2") (pinfunction "2_2") (pintype "passive"))
      (node (ref "C122") (pin "2") (pinfunction "2_2") (pintype "passive"))
      (node (ref "C125") (pin "1") (pinfunction "1_1") (pintype "passive"))
      (node (ref "C126") (pin "1") (pinfunction "1_1") (pintype "passive"))
      (node (ref "C127") (pin "1") (pinfunction "1_1") (pintype "passive"))
      (node (ref "C128") (pin "1") (pinfunction "1_1") (pintype "passive"))
      (node (ref "C129") (pin "1") (pinfunction "1_1") (pintype "passive"))
      (node (ref "C130") (pin "1") (pinfunction "1_1") (pintype "passive"))
      (node (ref "C131") (pin "1") (pinfunction "1_1") (pintype "passive"))
      (node (ref "C132") (pin "1") (pinfunction "1_1") (pintype "passive"))
      (node (ref "C134") (pin "1") (pinfunction "1_1") (pintype "passive"))
      (node (ref "C135") (pin "1") (pinfunction "1_1") (pintype "passive"))
      (node (ref "R115") (pin "2") (pinfunction "2_2") (pintype "passive"))
      (node (ref "R116") (pin "2") (pinfunction "2_2") (pintype "passive"))
      (node (ref "R117") (pin "2") (pinfunction "2_2") (pintype "passive"))
      (node (ref "R118") (pin "2") (pinfunction "2_2") (pintype "passive"))
      (node (ref "R121") (pin "2") (pinfunction "2_2") (pintype "passive"))
      (node (ref "R122") (pin "2") (pinfunction "2_2") (pintype "passive"))
      (node (ref "R123") (pin "2") (pinfunction "2_2") (pintype "passive"))
      (node (ref "R124") (pin "2") (pinfunction "2_2") (pintype "passive"))
      (node (ref "R126") (pin "2") (pinfunction "2_2") (pintype "passive"))
      (node (ref "R128") (pin "2") (pinfunction "2_2") (pintype "passive"))
      (node (ref "R130") (pin "2") (pinfunction "2_2") (pintype "passive"))
      (node (ref "R131") (pin "2") (pinfunction "2_2") (pintype "passive"))
      (node (ref "R132") (pin "2") (pinfunction "2_2") (pintype "passive"))
      (node (ref "R133") (pin "2") (pinfunction "2_2") (pintype "passive"))
      (node (ref "R135") (pin "2") (pinfunction "2_2") (pintype "passive"))
      (node (ref "R138") (pin "2") (pinfunction "2_2") (pintype "passive"))
      (node (ref "R141") (pin "2") (pinfunction "2_2") (pintype "passive"))
      (node (ref "R142") (pin "2") (pinfunction "2_2") (pintype "passive"))
      (node (ref "R143") (pin "2") (pinfunction "2_2") (pintype "passive"))
      (node (ref "R144") (pin "2") (pinfunction "2_2") (pintype "passive"))
      (node (ref "R145") (pin "2") (pinfunction "2_2") (pintype "passive"))
      (node (ref "R146") (pin "2") (pinfunction "2_2") (pintype "passive"))
      (node (ref "R147") (pin "2") (pinfunction "2_2") (pintype "passive"))
      (node (ref "R148") (pin "2") (pinfunction "2_2") (pintype "passive"))
    )
    (net (code "59") (name "unconnected-(U5-NC-PadJ1)") (class "Default")
      (node (ref "U5") (pin "J1") (pinfunction "NC_J1") (pintype "passive+no_connect"))
    )
    (net (code "60") (name "unconnected-(U5-NC-PadJ9)") (class "Default")
      (node (ref "U5") (pin "J9") (pinfunction "NC_J9") (pintype "passive+no_connect"))
    )
    (net (code "61") (name "unconnected-(U5-NC-PadL1)") (class "Default")
      (node (ref "U5") (pin "L1") (pinfunction "NC_L1") (pintype "passive+no_connect"))
    )
    (net (code "62") (name "unconnected-(U5-NC-PadL9)") (class "Default")
      (node (ref "U5") (pin "L9") (pinfunction "NC_L9") (pintype "passive+no_connect"))
    )
    (net (code "63") (name "unconnected-(U5-NC-PadM7)") (class "Default")
      (node (ref "U5") (pin "M7") (pinfunction "NC_M7") (pintype "passive+no_connect"))
    )
  )
)
